# Adafruit_Circuit_Playground_Bluefruit.net
KiCad netlist of a schematic drawn in EAGLE
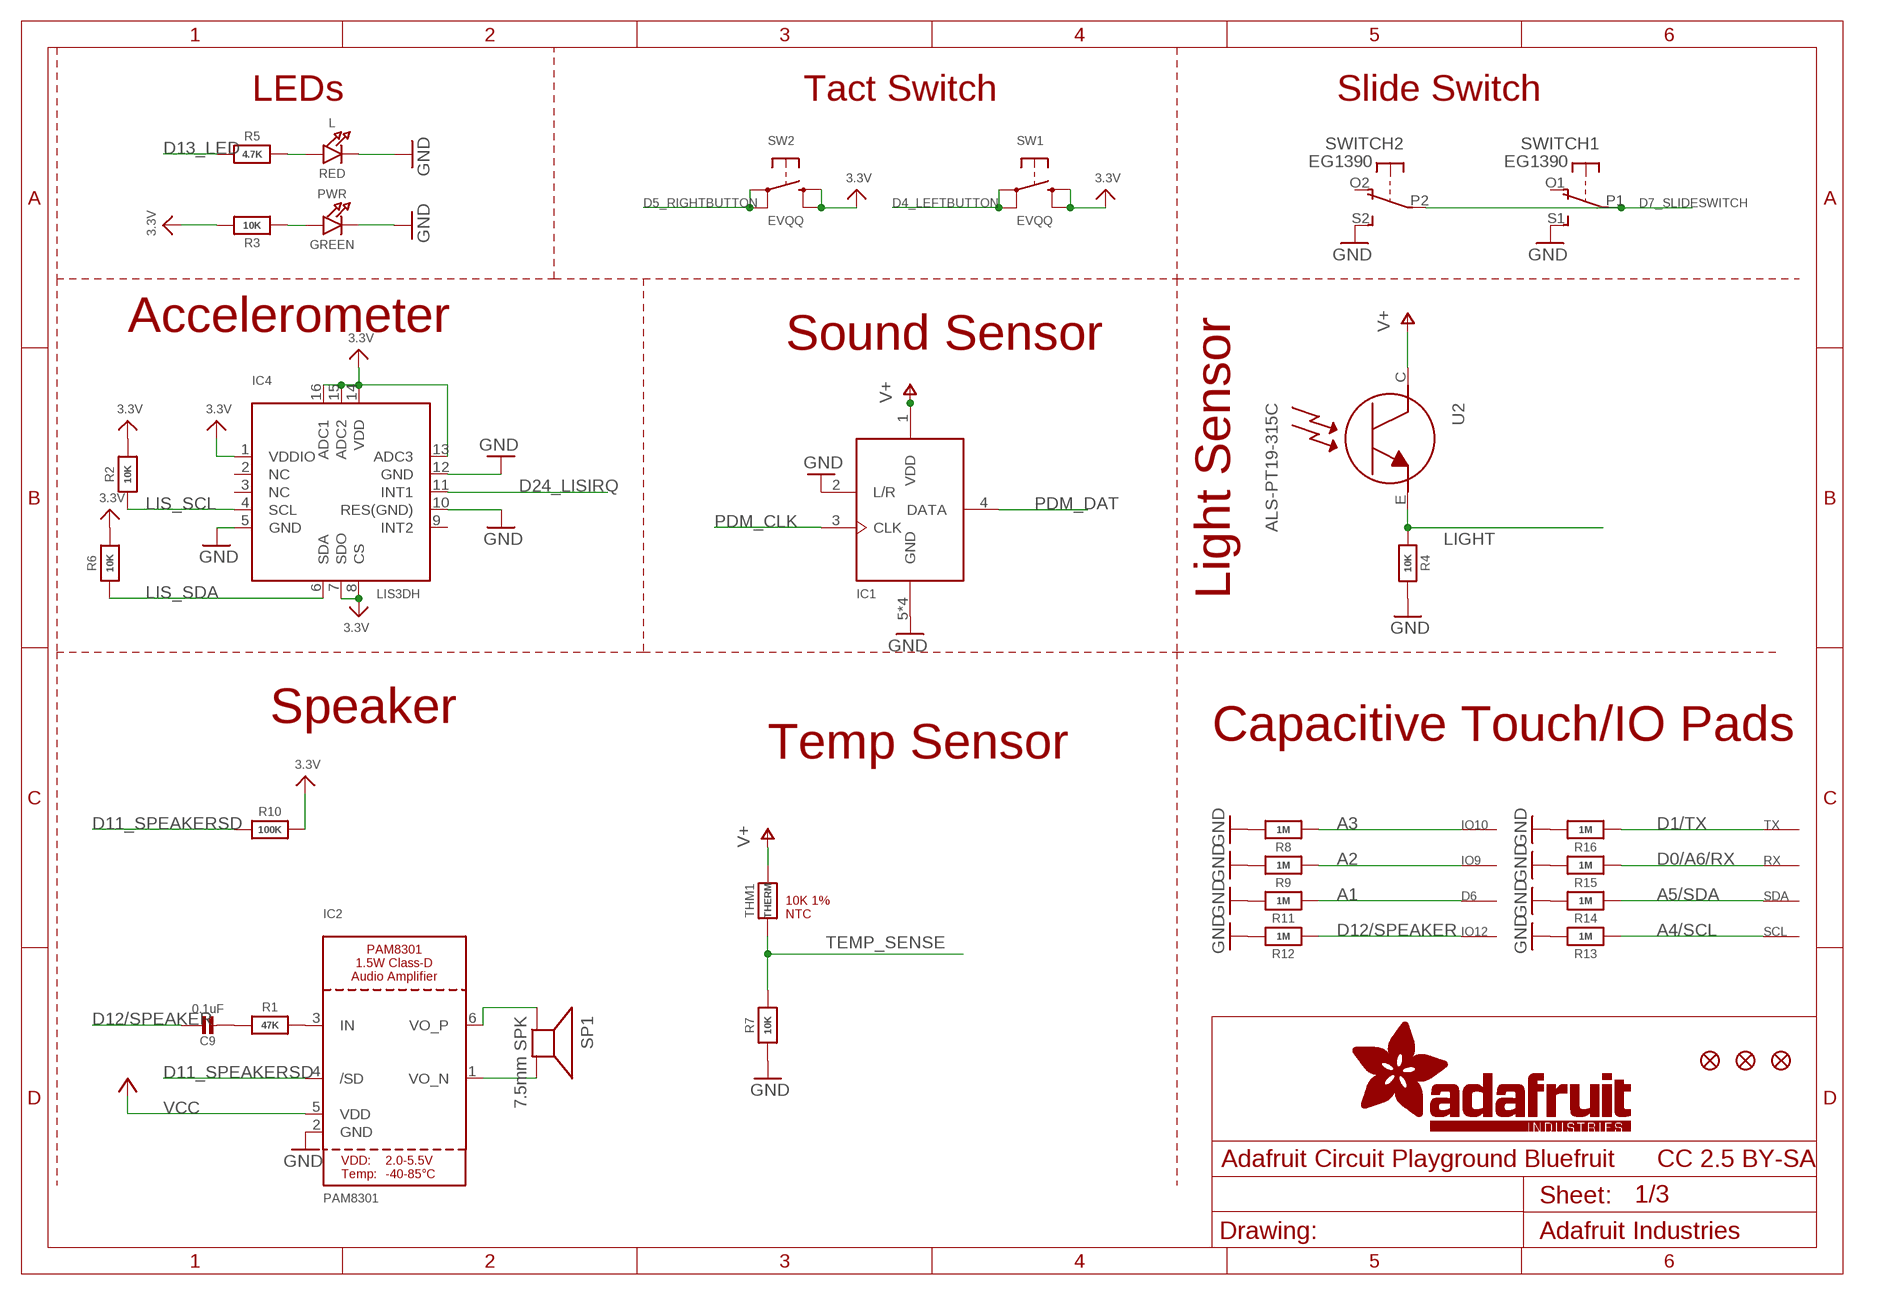
[diagram p0: schematic, sheet 1]
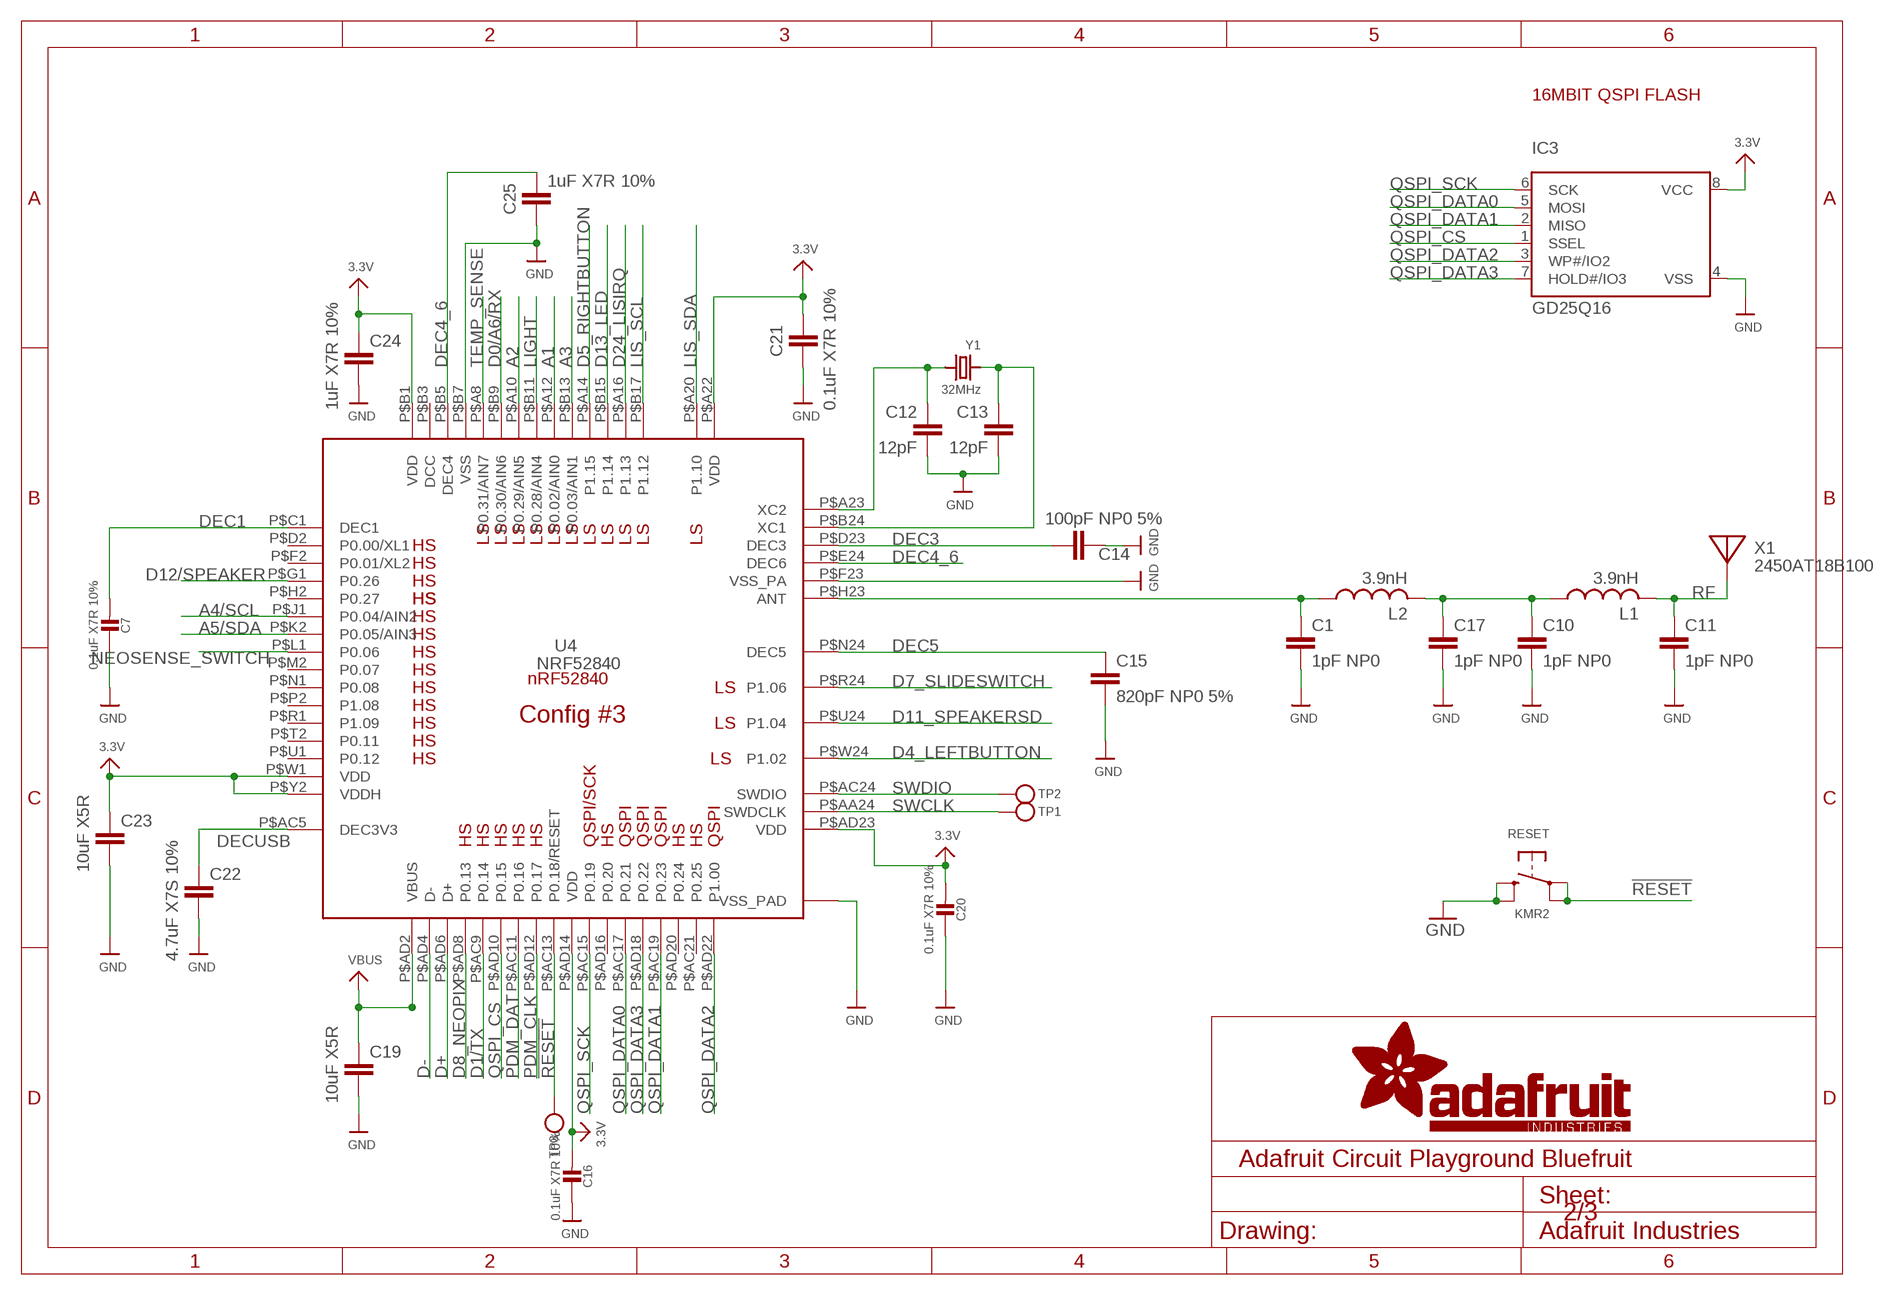
[diagram p1: schematic, sheet 2]
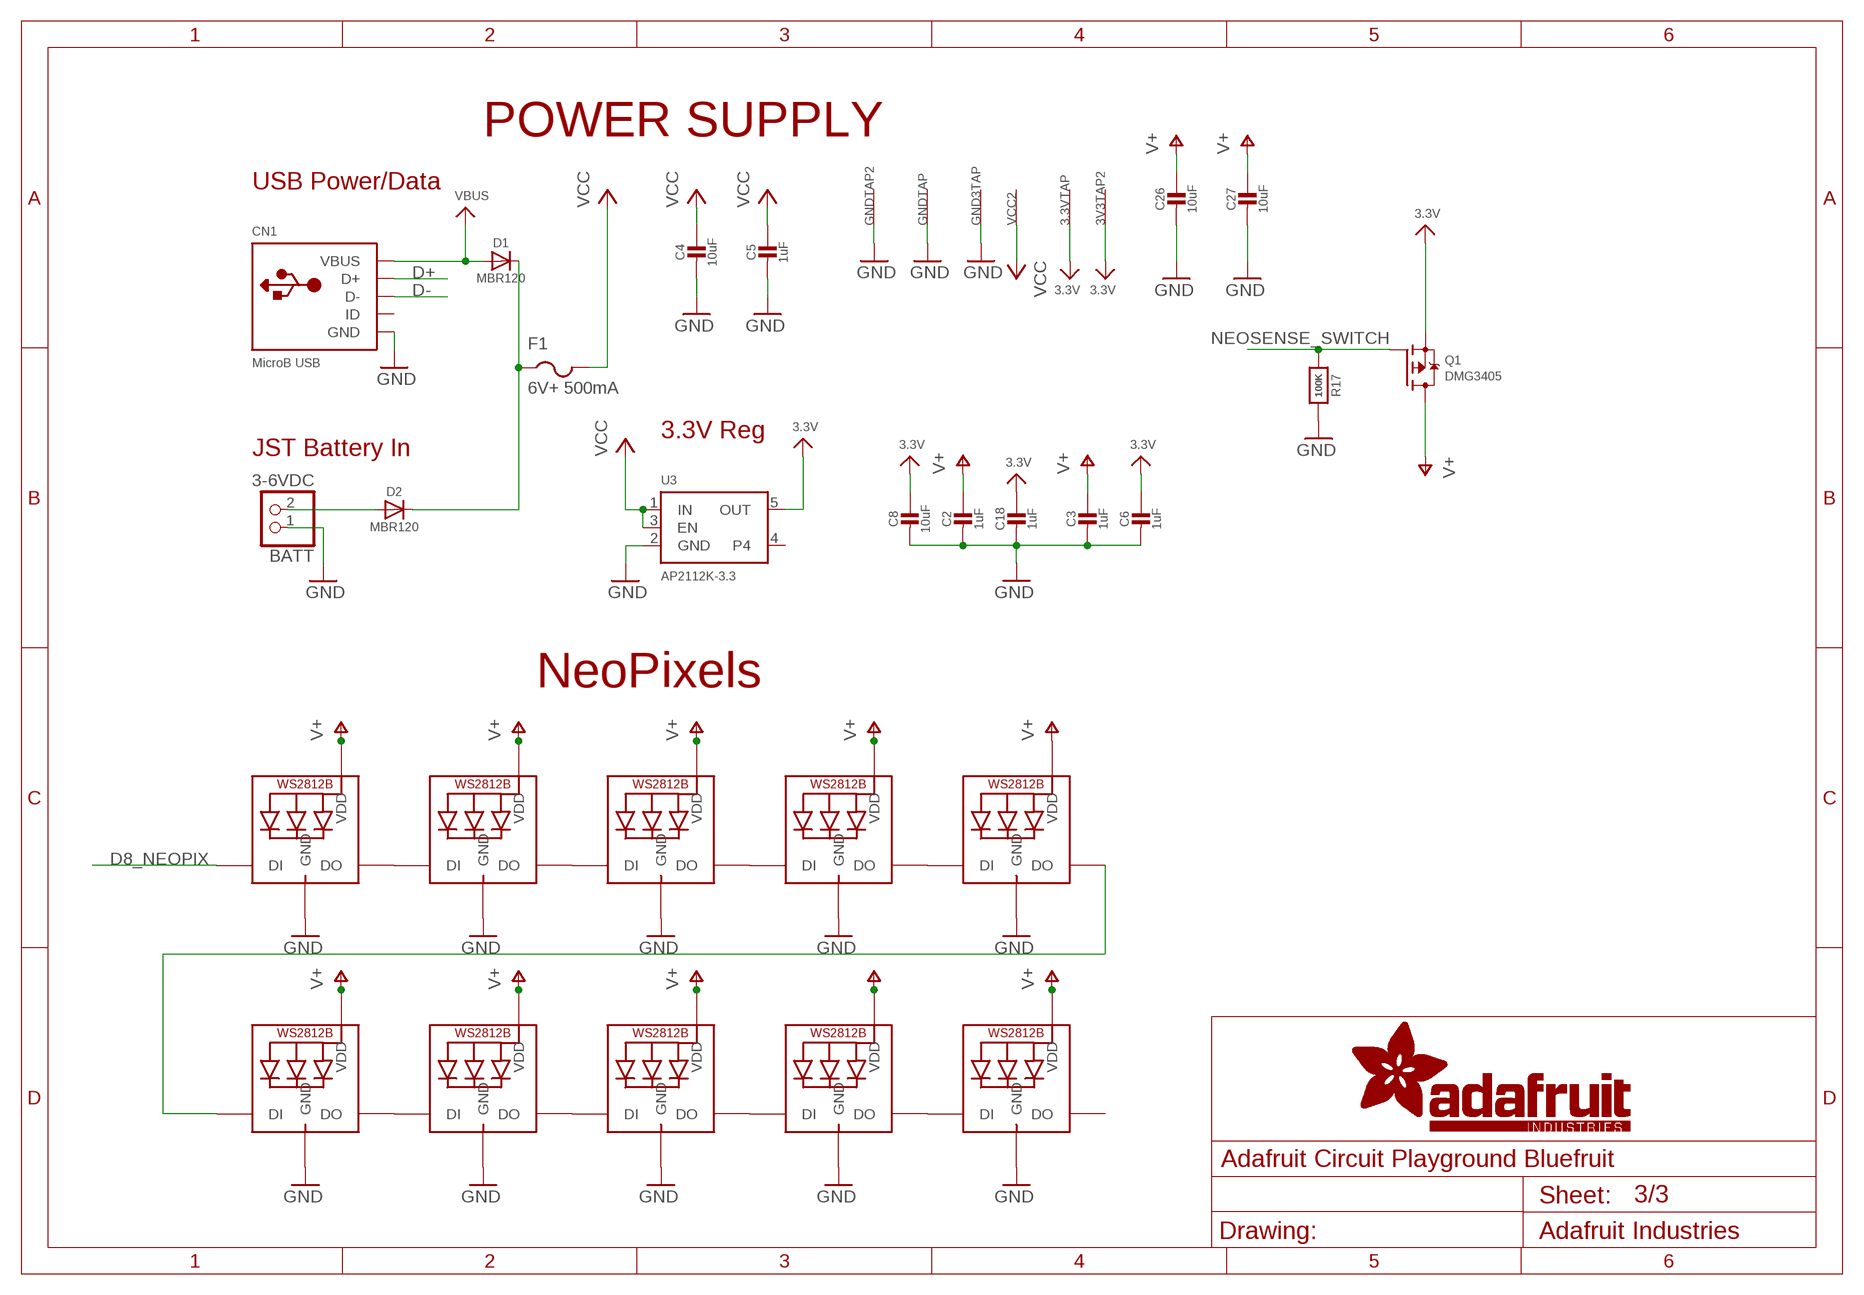
[diagram p2: schematic, sheet 3]

(export (version "E")
  (design (tool "Eeschema 10.0.6"))
  (components
    (comp (ref "C1")
      (value "1pF NP0")
      (footprint "eagle-import:RESC0402_N")
      (libsource (lib "eagle-import") (part "CAPACITOR_0402_N"))
    )
    (comp (ref "C7")
      (value "0.1uF X7R 10%")
      (footprint "eagle-import:0603-NO")
      (libsource (lib "eagle-import") (part "CAP_CERAMIC0603_NO"))
    )
    (comp (ref "C10")
      (value "1pF NP0")
      (footprint "eagle-import:RESC0402_N")
      (libsource (lib "eagle-import") (part "CAPACITOR_0402_N"))
    )
    (comp (ref "C11")
      (value "1pF NP0")
      (footprint "eagle-import:RESC0402_N")
      (libsource (lib "eagle-import") (part "CAPACITOR_0402_N"))
    )
    (comp (ref "C12")
      (value "12pF")
      (footprint "eagle-import:RESC0402_N")
      (libsource (lib "eagle-import") (part "CAPACITOR_0402_N"))
    )
    (comp (ref "C13")
      (value "12pF")
      (footprint "eagle-import:RESC0402_N")
      (libsource (lib "eagle-import") (part "CAPACITOR_0402_N"))
    )
    (comp (ref "C14")
      (value "100pF NP0 5%")
      (footprint "eagle-import:RESC0402_N")
      (libsource (lib "eagle-import") (part "CAPACITOR_0402_N"))
    )
    (comp (ref "C15")
      (value "820pF NP0 5%")
      (footprint "eagle-import:RESC0402_N")
      (libsource (lib "eagle-import") (part "CAPACITOR_0402_N"))
    )
    (comp (ref "C16")
      (value "0.1uF X7R 10%")
      (footprint "eagle-import:0603-NO")
      (libsource (lib "eagle-import") (part "CAP_CERAMIC0603_NO"))
    )
    (comp (ref "C17")
      (value "1pF NP0")
      (footprint "eagle-import:RESC0402_N")
      (libsource (lib "eagle-import") (part "CAPACITOR_0402_N"))
    )
    (comp (ref "C19")
      (value "10uF X5R")
      (footprint "eagle-import:RESC0805_N")
      (libsource (lib "eagle-import") (part "CAPACITOR_0805_N"))
    )
    (comp (ref "C20")
      (value "0.1uF X7R 10%")
      (footprint "eagle-import:0603-NO")
      (libsource (lib "eagle-import") (part "CAP_CERAMIC0603_NO"))
    )
    (comp (ref "C21")
      (value "0.1uF X7R 10%")
      (footprint "eagle-import:RESC0603_L")
      (libsource (lib "eagle-import") (part "CAPACITOR_0603_L"))
    )
    (comp (ref "C22")
      (value "4.7uF X7S 10%")
      (footprint "eagle-import:RESC0805_N")
      (libsource (lib "eagle-import") (part "CAPACITOR_0805_N"))
    )
    (comp (ref "C23")
      (value "10uF X5R")
      (footprint "eagle-import:RESC0805_N")
      (libsource (lib "eagle-import") (part "CAPACITOR_0805_N"))
    )
    (comp (ref "C24")
      (value "1uF X7R 10%")
      (footprint "eagle-import:RESC0603_N")
      (libsource (lib "eagle-import") (part "CAPACITOR_0603_N"))
    )
    (comp (ref "C25")
      (value "1uF X7R 10%")
      (footprint "eagle-import:RESC0603_N")
      (libsource (lib "eagle-import") (part "CAPACITOR_0603_N"))
    )
    (comp (ref "IC3")
      (value "GD25Q16")
      (footprint "eagle-import:USON8")
      (libsource (lib "eagle-import") (part "SPIFLASH_8PINUX"))
    )
    (comp (ref "L1")
      (value "3.9nH")
      (footprint "eagle-import:RESC0402_N")
      (libsource (lib "eagle-import") (part "INDUCTOR_0402_N"))
    )
    (comp (ref "L2")
      (value "3.9nH")
      (footprint "eagle-import:RESC0402_N")
      (libsource (lib "eagle-import") (part "INDUCTOR_0402_N"))
    )
    (comp (ref "RESET")
      (value "KMR2")
      (footprint "eagle-import:BTN_KMR2_4.6X2.8")
      (libsource (lib "eagle-import") (part "SWITCH_TACT_SMT4.6X2.8"))
    )
    (comp (ref "TP1")
      (value "TESTPOINTROUND1.5MMNO")
      (footprint "eagle-import:TESTPOINT_ROUND_1.5MM_NO")
      (libsource (lib "eagle-import") (part "TESTPOINTROUND1.5MMNO"))
    )
    (comp (ref "TP2")
      (value "TESTPOINTROUND1.5MMNO")
      (footprint "eagle-import:TESTPOINT_ROUND_1.5MM_NO")
      (libsource (lib "eagle-import") (part "TESTPOINTROUND1.5MMNO"))
    )
    (comp (ref "TP3")
      (value "TESTPOINTROUND1.5MMNO")
      (footprint "eagle-import:TESTPOINT_ROUND_1.5MM_NO")
      (libsource (lib "eagle-import") (part "TESTPOINTROUND1.5MMNO"))
    )
    (comp (ref "U4")
      (value "NRF52840")
      (footprint "eagle-import:AQFN50P700X800X85_HS-74N_SMALLCENTER")
      (libsource (lib "eagle-import") (part "NRF52840_CPB_SMALLCENTER"))
    )
    (comp (ref "X1")
      (value "2450AT18B100")
      (footprint "eagle-import:ANT_2450AT18B100")
      (libsource (lib "eagle-import") (part "ANTENNA_JOHANSON_2450AT18B100"))
    )
    (comp (ref "Y1")
      (value "32MHz")
      (footprint "eagle-import:CRYSTAL_2X1.6")
      (libsource (lib "eagle-import") (part "CRYSTAL_2X1.6MM"))
    )
    (comp (ref "C9")
      (value "0.1uF")
      (footprint "eagle-import:0603-NO")
      (libsource (lib "eagle-import") (part "CAP_CERAMIC0603_NO"))
    )
    (comp (ref "D6")
      (value "SEWTAP-ALLIGATOR")
      (footprint "eagle-import:SEWALLI")
      (libsource (lib "eagle-import") (part "SEWTAP-ALLIGATOR"))
    )
    (comp (ref "IC1")
      (value "MIC_PDM")
      (footprint "eagle-import:SPK0415HM4H")
      (libsource (lib "eagle-import") (part "MIC_PDM_SPK0415"))
    )
    (comp (ref "IC2")
      (value "PAM8301")
      (footprint "eagle-import:SOT23-6")
      (libsource (lib "eagle-import") (part "PAM8301"))
    )
    (comp (ref "IC4")
      (value "LIS3DH")
      (footprint "eagle-import:LGA16_3X3MM")
      (libsource (lib "eagle-import") (part "ACCEL_LIS3DHTR"))
    )
    (comp (ref "IO9")
      (value "SEWTAP-ALLIGATOR")
      (footprint "eagle-import:SEWALLI")
      (libsource (lib "eagle-import") (part "SEWTAP-ALLIGATOR"))
    )
    (comp (ref "IO10")
      (value "SEWTAP-ALLIGATOR")
      (footprint "eagle-import:SEWALLI")
      (libsource (lib "eagle-import") (part "SEWTAP-ALLIGATOR"))
    )
    (comp (ref "IO12")
      (value "SEWTAP-ALLIGATOR")
      (footprint "eagle-import:SEWALLI")
      (libsource (lib "eagle-import") (part "SEWTAP-ALLIGATOR"))
    )
    (comp (ref "L")
      (value "RED")
      (footprint "eagle-import:CHIPLED_0603_NOOUTLINE")
      (libsource (lib "eagle-import") (part "LED0603_NOOUTLINE"))
    )
    (comp (ref "PWR")
      (value "GREEN")
      (footprint "eagle-import:CHIPLED_0603_NOOUTLINE")
      (libsource (lib "eagle-import") (part "LED0603_NOOUTLINE"))
    )
    (comp (ref "R1")
      (value "47K")
      (footprint "eagle-import:0603-NO")
      (libsource (lib "eagle-import") (part "RESISTOR_0603_NOOUT"))
    )
    (comp (ref "R2")
      (value "10K")
      (footprint "eagle-import:0603-NO")
      (libsource (lib "eagle-import") (part "RESISTOR_0603_NOOUT"))
    )
    (comp (ref "R3")
      (value "10K")
      (footprint "eagle-import:0603-NO")
      (libsource (lib "eagle-import") (part "RESISTOR_0603_NOOUT"))
    )
    (comp (ref "R4")
      (value "10K")
      (footprint "eagle-import:0603-NO")
      (libsource (lib "eagle-import") (part "RESISTOR_0603_NOOUT"))
    )
    (comp (ref "R5")
      (value "4.7K")
      (footprint "eagle-import:0603-NO")
      (libsource (lib "eagle-import") (part "RESISTOR_0603_NOOUT"))
    )
    (comp (ref "R6")
      (value "10K")
      (footprint "eagle-import:0603-NO")
      (libsource (lib "eagle-import") (part "RESISTOR_0603_NOOUT"))
    )
    (comp (ref "R7")
      (value "10K")
      (footprint "eagle-import:0603-NO")
      (libsource (lib "eagle-import") (part "RESISTOR_0603_NOOUT"))
    )
    (comp (ref "R8")
      (value "1M")
      (footprint "eagle-import:0603-NO")
      (libsource (lib "eagle-import") (part "RESISTOR_0603_NOOUT"))
    )
    (comp (ref "R9")
      (value "1M")
      (footprint "eagle-import:0603-NO")
      (libsource (lib "eagle-import") (part "RESISTOR_0603_NOOUT"))
    )
    (comp (ref "R10")
      (value "100K")
      (footprint "eagle-import:0603-NO")
      (libsource (lib "eagle-import") (part "RESISTOR_0603_NOOUT"))
    )
    (comp (ref "R11")
      (value "1M")
      (footprint "eagle-import:0603-NO")
      (libsource (lib "eagle-import") (part "RESISTOR_0603_NOOUT"))
    )
    (comp (ref "R12")
      (value "1M")
      (footprint "eagle-import:0603-NO")
      (libsource (lib "eagle-import") (part "RESISTOR_0603_NOOUT"))
    )
    (comp (ref "R13")
      (value "1M")
      (footprint "eagle-import:0603-NO")
      (libsource (lib "eagle-import") (part "RESISTOR_0603_NOOUT"))
    )
    (comp (ref "R14")
      (value "1M")
      (footprint "eagle-import:0603-NO")
      (libsource (lib "eagle-import") (part "RESISTOR_0603_NOOUT"))
    )
    (comp (ref "R15")
      (value "1M")
      (footprint "eagle-import:0603-NO")
      (libsource (lib "eagle-import") (part "RESISTOR_0603_NOOUT"))
    )
    (comp (ref "R16")
      (value "1M")
      (footprint "eagle-import:0603-NO")
      (libsource (lib "eagle-import") (part "RESISTOR_0603_NOOUT"))
    )
    (comp (ref "RX")
      (value "SEWTAP-ALLIGATOR")
      (footprint "eagle-import:SEWALLI")
      (libsource (lib "eagle-import") (part "SEWTAP-ALLIGATOR"))
    )
    (comp (ref "SCL")
      (value "SEWTAP-ALLIGATOR")
      (footprint "eagle-import:SEWALLI")
      (libsource (lib "eagle-import") (part "SEWTAP-ALLIGATOR"))
    )
    (comp (ref "SDA")
      (value "SEWTAP-ALLIGATOR")
      (footprint "eagle-import:SEWALLI")
      (libsource (lib "eagle-import") (part "SEWTAP-ALLIGATOR"))
    )
    (comp (ref "SP1")
      (value "7.5mm SPK")
      (footprint "eagle-import:BUZZER_SMT_7.5MM")
      (libsource (lib "eagle-import") (part "SPEAKER_7.5MM"))
    )
    (comp (ref "SW1")
      (value "EVQQ")
      (footprint "eagle-import:EVQ-Q2_SMALLER")
      (libsource (lib "eagle-import") (part "SWITCH_TACT_SMT_EVQQ2_SMALL"))
    )
    (comp (ref "SW2")
      (value "EVQQ")
      (footprint "eagle-import:EVQ-Q2_SMALLER")
      (libsource (lib "eagle-import") (part "SWITCH_TACT_SMT_EVQQ2_SMALL"))
    )
    (comp (ref "SWITCH")
      (value "EG1390")
      (footprint "eagle-import:EG1390")
      (libsource (lib "eagle-import") (part "DPDT-EG1390"))
    )
    (comp (ref "THM1")
      (value "THERM")
      (footprint "eagle-import:_0402")
      (libsource (lib "eagle-import") (part "RESISTOR_0402"))
    )
    (comp (ref "TX")
      (value "SEWTAP-ALLIGATOR")
      (footprint "eagle-import:SEWALLI")
      (libsource (lib "eagle-import") (part "SEWTAP-ALLIGATOR"))
    )
    (comp (ref "U$2")
      (value "FIDUCIAL_1MM")
      (footprint "eagle-import:FIDUCIAL_1MM")
      (libsource (lib "eagle-import") (part "FIDUCIAL_1MM"))
    )
    (comp (ref "U$3")
      (value "FIDUCIAL_1MM")
      (footprint "eagle-import:FIDUCIAL_1MM")
      (fields (field (name "BOM") "EXCLUDE"))
      (libsource (lib "eagle-import") (part "FIDUCIAL_1MM"))
    )
    (comp (ref "U$6")
      (value "FIDUCIAL_1MM")
      (footprint "eagle-import:FIDUCIAL_1MM")
      (libsource (lib "eagle-import") (part "FIDUCIAL_1MM"))
    )
    (comp (ref "U2")
      (value "ALS-PT19-315C")
      (footprint "eagle-import:ALS-PT19-315C")
      (libsource (lib "eagle-import") (part "PHOTOTRANSISTOR_PT19-315C"))
    )
    (comp (ref "3.3VTAP")
      (value "SEWTAP-ALLIGATOR")
      (footprint "eagle-import:SEWALLI")
      (libsource (lib "eagle-import") (part "SEWTAP-ALLIGATOR"))
    )
    (comp (ref "3V3TAP2")
      (value "SEWTAP-ALLIGATOR")
      (footprint "eagle-import:SEWALLI")
      (libsource (lib "eagle-import") (part "SEWTAP-ALLIGATOR"))
    )
    (comp (ref "BATT")
      (value "3-6VDC")
      (footprint "eagle-import:JSTPH2")
      (libsource (lib "eagle-import") (part "CON_JST_PH_2PIN"))
    )
    (comp (ref "C2")
      (value "1uF")
      (footprint "eagle-import:0603-NO")
      (libsource (lib "eagle-import") (part "CAP_CERAMIC0603_NO"))
    )
    (comp (ref "C3")
      (value "1uF")
      (footprint "eagle-import:0603-NO")
      (libsource (lib "eagle-import") (part "CAP_CERAMIC0603_NO"))
    )
    (comp (ref "C4")
      (value "10uF")
      (footprint "eagle-import:0805-NO")
      (libsource (lib "eagle-import") (part "CAP_CERAMIC0805-NOOUTLINE"))
    )
    (comp (ref "C5")
      (value "1uF")
      (footprint "eagle-import:0603-NO")
      (libsource (lib "eagle-import") (part "CAP_CERAMIC0603_NO"))
    )
    (comp (ref "C6")
      (value "1uF")
      (footprint "eagle-import:0603-NO")
      (libsource (lib "eagle-import") (part "CAP_CERAMIC0603_NO"))
    )
    (comp (ref "C8")
      (value "10uF")
      (footprint "eagle-import:0805-NO")
      (libsource (lib "eagle-import") (part "CAP_CERAMIC0805-NOOUTLINE"))
    )
    (comp (ref "C18")
      (value "1uF")
      (footprint "eagle-import:0603-NO")
      (libsource (lib "eagle-import") (part "CAP_CERAMIC0603_NO"))
    )
    (comp (ref "C26")
      (value "10uF")
      (footprint "eagle-import:0805-NO")
      (libsource (lib "eagle-import") (part "CAP_CERAMIC0805-NOOUTLINE"))
    )
    (comp (ref "C27")
      (value "10uF")
      (footprint "eagle-import:0805-NO")
      (libsource (lib "eagle-import") (part "CAP_CERAMIC0805-NOOUTLINE"))
    )
    (comp (ref "CN1")
      (value "MicroB USB")
      (footprint "eagle-import:4UCONN_20329_V2")
      (libsource (lib "eagle-import") (part "USB_MICRO_20329_V2"))
    )
    (comp (ref "D1")
      (value "MBR120")
      (footprint "eagle-import:SOD-123")
      (libsource (lib "eagle-import") (part "DIODESOD-123"))
    )
    (comp (ref "D2")
      (value "MBR120")
      (footprint "eagle-import:SOD-123")
      (libsource (lib "eagle-import") (part "DIODESOD-123"))
    )
    (comp (ref "F1")
      (value "6V+ 500mA")
      (footprint "eagle-import:R1206")
      (libsource (lib "eagle-import") (part "PTCFUSE-1206"))
    )
    (comp (ref "GND3TAP")
      (value "SEWTAP-ALLIGATOR")
      (footprint "eagle-import:SEWALLI")
      (libsource (lib "eagle-import") (part "SEWTAP-ALLIGATOR"))
    )
    (comp (ref "GNDTAP")
      (value "SEWTAP-ALLIGATOR")
      (footprint "eagle-import:SEWALLI")
      (libsource (lib "eagle-import") (part "SEWTAP-ALLIGATOR"))
    )
    (comp (ref "GNDTAP2")
      (value "SEWTAP-ALLIGATOR")
      (footprint "eagle-import:SEWALLI")
      (libsource (lib "eagle-import") (part "SEWTAP-ALLIGATOR"))
    )
    (comp (ref "LED1")
      (value "WS2812B3535")
      (footprint "eagle-import:LED3535")
      (libsource (lib "eagle-import") (part "WS2812B3535"))
    )
    (comp (ref "LED2")
      (value "WS2812B3535")
      (footprint "eagle-import:LED3535")
      (libsource (lib "eagle-import") (part "WS2812B3535"))
    )
    (comp (ref "LED3")
      (value "WS2812B3535")
      (footprint "eagle-import:LED3535")
      (libsource (lib "eagle-import") (part "WS2812B3535"))
    )
    (comp (ref "LED4")
      (value "WS2812B3535")
      (footprint "eagle-import:LED3535")
      (libsource (lib "eagle-import") (part "WS2812B3535"))
    )
    (comp (ref "LED5")
      (value "WS2812B3535")
      (footprint "eagle-import:LED3535")
      (libsource (lib "eagle-import") (part "WS2812B3535"))
    )
    (comp (ref "LED6")
      (value "WS2812B3535")
      (footprint "eagle-import:LED3535")
      (libsource (lib "eagle-import") (part "WS2812B3535"))
    )
    (comp (ref "LED7")
      (value "WS2812B3535")
      (footprint "eagle-import:LED3535")
      (libsource (lib "eagle-import") (part "WS2812B3535"))
    )
    (comp (ref "LED8")
      (value "WS2812B3535")
      (footprint "eagle-import:LED3535")
      (libsource (lib "eagle-import") (part "WS2812B3535"))
    )
    (comp (ref "LED9")
      (value "WS2812B3535")
      (footprint "eagle-import:LED3535")
      (libsource (lib "eagle-import") (part "WS2812B3535"))
    )
    (comp (ref "LED10")
      (value "WS2812B3535")
      (footprint "eagle-import:LED3535")
      (libsource (lib "eagle-import") (part "WS2812B3535"))
    )
    (comp (ref "Q1")
      (value "DMG3405")
      (footprint "eagle-import:SOT23-R")
      (libsource (lib "eagle-import") (part "MOSFET-P"))
    )
    (comp (ref "R17")
      (value "100K")
      (footprint "eagle-import:0603-NO")
      (libsource (lib "eagle-import") (part "RESISTOR_0603_NOOUT"))
    )
    (comp (ref "U3")
      (value "AP2112K-3.3")
      (footprint "eagle-import:SOT23-5")
      (libsource (lib "eagle-import") (part "VREG_SOT23-5"))
    )
    (comp (ref "VCC2")
      (value "SEWTAP-ALLIGATOR")
      (footprint "eagle-import:SEWALLI")
      (libsource (lib "eagle-import") (part "SEWTAP-ALLIGATOR"))
    )
  )
  (nets
    (net (code "1") (name "3.3V") (class "Default")
      (node (ref "3.3VTAP") (pin "P$1") (pinfunction "SEW_P$1") (pintype "bidirectional"))
      (node (ref "3V3TAP2") (pin "P$1") (pinfunction "SEW_P$1") (pintype "bidirectional"))
      (node (ref "C16") (pin "2") (pinfunction "2_2") (pintype "passive"))
      (node (ref "C18") (pin "1") (pinfunction "1_1") (pintype "passive"))
      (node (ref "C20") (pin "2") (pinfunction "2_2") (pintype "passive"))
      (node (ref "C21") (pin "1") (pinfunction "1_1") (pintype "passive"))
      (node (ref "C23") (pin "1") (pinfunction "1_1") (pintype "passive"))
      (node (ref "C24") (pin "1") (pinfunction "1_1") (pintype "passive"))
      (node (ref "C6") (pin "1") (pinfunction "1_1") (pintype "passive"))
      (node (ref "C8") (pin "1") (pinfunction "1_1") (pintype "passive"))
      (node (ref "IC3") (pin "8") (pinfunction "VCC_8") (pintype "bidirectional"))
      (node (ref "IC4") (pin "1") (pinfunction "VDDIO_1") (pintype "power_in"))
      (node (ref "IC4") (pin "13") (pinfunction "ADC3_13") (pintype "input"))
      (node (ref "IC4") (pin "14") (pinfunction "VDD_14") (pintype "power_in"))
      (node (ref "IC4") (pin "15") (pinfunction "ADC2_15") (pintype "input"))
      (node (ref "IC4") (pin "16") (pinfunction "ADC1_16") (pintype "input"))
      (node (ref "IC4") (pin "7") (pinfunction "SDO_7") (pintype "bidirectional"))
      (node (ref "IC4") (pin "8") (pinfunction "CS_8") (pintype "input"))
      (node (ref "Q1") (pin "2") (pinfunction "S_2") (pintype "passive"))
      (node (ref "R10") (pin "2") (pinfunction "2_2") (pintype "passive"))
      (node (ref "R2") (pin "2") (pinfunction "2_2") (pintype "passive"))
      (node (ref "R3") (pin "2") (pinfunction "2_2") (pintype "passive"))
      (node (ref "R6") (pin "2") (pinfunction "2_2") (pintype "passive"))
      (node (ref "SW1") (pin "B") (pinfunction "S_B") (pintype "passive"))
      (node (ref "SW1") (pin "B'") (pinfunction "S1_B'") (pintype "passive"))
      (node (ref "SW2") (pin "B") (pinfunction "S_B") (pintype "passive"))
      (node (ref "SW2") (pin "B'") (pinfunction "S1_B'") (pintype "passive"))
      (node (ref "U3") (pin "5") (pinfunction "OUT_5") (pintype "power_in"))
      (node (ref "U4") (pin "P$A22") (pinfunction "VDD_P$A22") (pintype "power_in"))
      (node (ref "U4") (pin "P$AD14") (pinfunction "VDD_P$AD14") (pintype "power_in"))
      (node (ref "U4") (pin "P$AD23") (pinfunction "VDD_P$AD23") (pintype "power_in"))
      (node (ref "U4") (pin "P$B1") (pinfunction "VDD_P$B1") (pintype "power_in"))
      (node (ref "U4") (pin "P$W1") (pinfunction "VDD_P$W1") (pintype "power_in"))
      (node (ref "U4") (pin "P$Y2") (pinfunction "VDDH_P$Y2") (pintype "power_in"))
    )
    (net (code "2") (name "A1") (class "Default")
      (node (ref "D6") (pin "P$1") (pinfunction "SEW_P$1") (pintype "bidirectional"))
      (node (ref "R11") (pin "1") (pinfunction "1_1") (pintype "passive"))
      (node (ref "U4") (pin "P$A12") (pinfunction "P0.02/AIN0_P$A12") (pintype "bidirectional"))
    )
    (net (code "3") (name "A2") (class "Default")
      (node (ref "IO9") (pin "P$1") (pinfunction "SEW_P$1") (pintype "bidirectional"))
      (node (ref "R9") (pin "1") (pinfunction "1_1") (pintype "passive"))
      (node (ref "U4") (pin "P$A10") (pinfunction "P0.29/AIN5_P$A10") (pintype "bidirectional"))
    )
    (net (code "4") (name "A3") (class "Default")
      (node (ref "IO10") (pin "P$1") (pinfunction "SEW_P$1") (pintype "bidirectional"))
      (node (ref "R8") (pin "1") (pinfunction "1_1") (pintype "passive"))
      (node (ref "U4") (pin "P$B13") (pinfunction "P0.03/AIN1_P$B13") (pintype "bidirectional"))
    )
    (net (code "5") (name "A4{slash}SCL") (class "Default")
      (node (ref "R13") (pin "1") (pinfunction "1_1") (pintype "passive"))
      (node (ref "SCL") (pin "P$1") (pinfunction "SEW_P$1") (pintype "bidirectional"))
      (node (ref "U4") (pin "P$J1") (pinfunction "P0.04/AIN2_P$J1") (pintype "bidirectional"))
    )
    (net (code "6") (name "A5{slash}SDA") (class "Default")
      (node (ref "R14") (pin "1") (pinfunction "1_1") (pintype "passive"))
      (node (ref "SDA") (pin "P$1") (pinfunction "SEW_P$1") (pintype "bidirectional"))
      (node (ref "U4") (pin "P$K2") (pinfunction "P0.05/AIN3_P$K2") (pintype "bidirectional"))
    )
    (net (code "7") (name "D+") (class "Default")
      (node (ref "CN1") (pin "D+") (pinfunction "D+_D+") (pintype "bidirectional"))
      (node (ref "U4") (pin "P$AD6") (pinfunction "D+_P$AD6") (pintype "bidirectional"))
    )
    (net (code "8") (name "D-") (class "Default")
      (node (ref "CN1") (pin "D-") (pinfunction "D-_D-") (pintype "bidirectional"))
      (node (ref "U4") (pin "P$AD4") (pinfunction "D-_P$AD4") (pintype "bidirectional"))
    )
    (net (code "9") (name "D0{slash}A6{slash}RX") (class "Default")
      (node (ref "R15") (pin "1") (pinfunction "1_1") (pintype "passive"))
      (node (ref "RX") (pin "P$1") (pinfunction "SEW_P$1") (pintype "bidirectional"))
      (node (ref "U4") (pin "P$B9") (pinfunction "P0.30/AIN6_P$B9") (pintype "bidirectional"))
    )
    (net (code "10") (name "D1{slash}TX") (class "Default")
      (node (ref "R16") (pin "1") (pinfunction "1_1") (pintype "passive"))
      (node (ref "TX") (pin "P$1") (pinfunction "SEW_P$1") (pintype "bidirectional"))
      (node (ref "U4") (pin "P$AC9") (pinfunction "P0.14_P$AC9") (pintype "bidirectional"))
    )
    (net (code "11") (name "D4_LEFTBUTTON") (class "Default")
      (node (ref "SW1") (pin "A") (pinfunction "P_A") (pintype "passive"))
      (node (ref "SW1") (pin "A'") (pinfunction "P1_A'") (pintype "passive"))
      (node (ref "U4") (pin "P$W24") (pinfunction "P1.02_P$W24") (pintype "bidirectional"))
    )
    (net (code "12") (name "D5_RIGHTBUTTON") (class "Default")
      (node (ref "SW2") (pin "A") (pinfunction "P_A") (pintype "passive"))
      (node (ref "SW2") (pin "A'") (pinfunction "P1_A'") (pintype "passive"))
      (node (ref "U4") (pin "P$A14") (pinfunction "P1.15_P$A14") (pintype "bidirectional"))
    )
    (net (code "13") (name "D7_SLIDESWITCH") (class "Default")
      (node (ref "SWITCH") (pin "P1") (pinfunction "P_P1") (pintype "passive"))
      (node (ref "SWITCH") (pin "P2") (pinfunction "P_P2") (pintype "passive"))
      (node (ref "U4") (pin "P$R24") (pinfunction "P1.06_P$R24") (pintype "bidirectional"))
    )
    (net (code "14") (name "D8_NEOPIX") (class "Default")
      (node (ref "LED6") (pin "1") (pinfunction "DI_1") (pintype "input"))
      (node (ref "U4") (pin "P$AD8") (pinfunction "P0.13_P$AD8") (pintype "bidirectional"))
    )
    (net (code "15") (name "D11_SPEAKERSD") (class "Default")
      (node (ref "IC2") (pin "4") (pinfunction "/SD_4") (pintype "input"))
      (node (ref "R10") (pin "1") (pinfunction "1_1") (pintype "passive"))
      (node (ref "U4") (pin "P$U24") (pinfunction "P1.04_P$U24") (pintype "bidirectional"))
    )
    (net (code "16") (name "D12{slash}SPEAKER") (class "Default")
      (node (ref "C9") (pin "1") (pinfunction "1_1") (pintype "passive"))
      (node (ref "IO12") (pin "P$1") (pinfunction "SEW_P$1") (pintype "bidirectional"))
      (node (ref "R12") (pin "1") (pinfunction "1_1") (pintype "passive"))
      (node (ref "U4") (pin "P$G1") (pinfunction "P0.26_P$G1") (pintype "bidirectional"))
    )
    (net (code "17") (name "D13_LED") (class "Default")
      (node (ref "R5") (pin "1") (pinfunction "1_1") (pintype "passive"))
      (node (ref "U4") (pin "P$B15") (pinfunction "P1.14_P$B15") (pintype "bidirectional"))
    )
    (net (code "18") (name "D24_LISIRQ") (class "Default")
      (node (ref "IC4") (pin "11") (pinfunction "INT1_11") (pintype "output"))
      (node (ref "U4") (pin "P$A16") (pinfunction "P1.13_P$A16") (pintype "bidirectional"))
    )
    (net (code "19") (name "DEC1") (class "Default")
      (node (ref "C7") (pin "2") (pinfunction "2_2") (pintype "passive"))
      (node (ref "U4") (pin "P$C1") (pinfunction "DEC1_P$C1") (pintype "power_in"))
    )
    (net (code "20") (name "DEC3") (class "Default")
      (node (ref "C14") (pin "1") (pinfunction "1_1") (pintype "passive"))
      (node (ref "U4") (pin "P$D23") (pinfunction "DEC3_P$D23") (pintype "bidirectional"))
    )
    (net (code "21") (name "DEC4_6") (class "Default")
      (node (ref "C25") (pin "1") (pinfunction "1_1") (pintype "passive"))
      (node (ref "U4") (pin "P$B5") (pinfunction "DEC4_P$B5") (pintype "power_in"))
      (node (ref "U4") (pin "P$E24") (pinfunction "DEC6_P$E24") (pintype "bidirectional"))
    )
    (net (code "22") (name "DEC5") (class "Default")
      (node (ref "C15") (pin "1") (pinfunction "1_1") (pintype "passive"))
      (node (ref "U4") (pin "P$N24") (pinfunction "DEC5_P$N24") (pintype "bidirectional"))
    )
    (net (code "23") (name "DECUSB") (class "Default")
      (node (ref "C22") (pin "1") (pinfunction "1_1") (pintype "passive"))
      (node (ref "U4") (pin "P$AC5") (pinfunction "DEC3V3_P$AC5") (pintype "bidirectional"))
    )
    (net (code "24") (name "GND") (class "Default")
      (node (ref "BATT") (pin "1") (pinfunction "1_1") (pintype "passive"))
      (node (ref "C1") (pin "2") (pinfunction "2_2") (pintype "passive"))
      (node (ref "C10") (pin "2") (pinfunction "2_2") (pintype "passive"))
      (node (ref "C11") (pin "2") (pinfunction "2_2") (pintype "passive"))
      (node (ref "C12") (pin "2") (pinfunction "2_2") (pintype "passive"))
      (node (ref "C13") (pin "2") (pinfunction "2_2") (pintype "passive"))
      (node (ref "C14") (pin "2") (pinfunction "2_2") (pintype "passive"))
      (node (ref "C15") (pin "2") (pinfunction "2_2") (pintype "passive"))
      (node (ref "C16") (pin "1") (pinfunction "1_1") (pintype "passive"))
      (node (ref "C17") (pin "2") (pinfunction "2_2") (pintype "passive"))
      (node (ref "C18") (pin "2") (pinfunction "2_2") (pintype "passive"))
      (node (ref "C19") (pin "2") (pinfunction "2_2") (pintype "passive"))
      (node (ref "C2") (pin "2") (pinfunction "2_2") (pintype "passive"))
      (node (ref "C20") (pin "1") (pinfunction "1_1") (pintype "passive"))
      (node (ref "C21") (pin "2") (pinfunction "2_2") (pintype "passive"))
      (node (ref "C22") (pin "2") (pinfunction "2_2") (pintype "passive"))
      (node (ref "C23") (pin "2") (pinfunction "2_2") (pintype "passive"))
      (node (ref "C24") (pin "2") (pinfunction "2_2") (pintype "passive"))
      (node (ref "C25") (pin "2") (pinfunction "2_2") (pintype "passive"))
      (node (ref "C26") (pin "2") (pinfunction "2_2") (pintype "passive"))
      (node (ref "C27") (pin "2") (pinfunction "2_2") (pintype "passive"))
      (node (ref "C3") (pin "2") (pinfunction "2_2") (pintype "passive"))
      (node (ref "C4") (pin "2") (pinfunction "2_2") (pintype "passive"))
      (node (ref "C5") (pin "2") (pinfunction "2_2") (pintype "passive"))
      (node (ref "C6") (pin "2") (pinfunction "2_2") (pintype "passive"))
      (node (ref "C7") (pin "1") (pinfunction "1_1") (pintype "passive"))
      (node (ref "C8") (pin "2") (pinfunction "2_2") (pintype "passive"))
      (node (ref "CN1") (pin "BASE@1") (pinfunction "GND_BASE@1") (pintype "power_in"))
      (node (ref "CN1") (pin "BASE@2") (pinfunction "GND_BASE@2") (pintype "power_in"))
      (node (ref "CN1") (pin "GND") (pinfunction "GND_GND") (pintype "power_in"))
      (node (ref "CN1") (pin "SPRT@1") (pinfunction "GND_SPRT@1") (pintype "power_in"))
      (node (ref "CN1") (pin "SPRT@2") (pinfunction "GND_SPRT@2") (pintype "power_in"))
      (node (ref "CN1") (pin "SPRT@3") (pinfunction "GND_SPRT@3") (pintype "power_in"))
      (node (ref "CN1") (pin "SPRT@4") (pinfunction "GND_SPRT@4") (pintype "power_in"))
      (node (ref "GND3TAP") (pin "P$1") (pinfunction "SEW_P$1") (pintype "bidirectional"))
      (node (ref "GNDTAP") (pin "P$1") (pinfunction "SEW_P$1") (pintype "bidirectional"))
      (node (ref "GNDTAP2") (pin "P$1") (pinfunction "SEW_P$1") (pintype "bidirectional"))
      (node (ref "IC1") (pin "2") (pinfunction "L/R_2") (pintype "input"))
      (node (ref "IC1") (pin "5") (pinfunction "GND_5") (pintype "power_in"))
      (node (ref "IC1") (pin "6") (pinfunction "GND_6") (pintype "power_in"))
      (node (ref "IC1") (pin "7") (pinfunction "GND_7") (pintype "power_in"))
      (node (ref "IC1") (pin "8") (pinfunction "GND_8") (pintype "power_in"))
      (node (ref "IC2") (pin "2") (pinfunction "GND_2") (pintype "power_in"))
      (node (ref "IC3") (pin "4") (pinfunction "VSS_4") (pintype "bidirectional"))
      (node (ref "IC4") (pin "10") (pinfunction "RES(GND)_10") (pintype "bidirectional"))
      (node (ref "IC4") (pin "12") (pinfunction "GND_12") (pintype "power_in"))
      (node (ref "IC4") (pin "5") (pinfunction "GND_5") (pintype "power_in"))
      (node (ref "L") (pin "C") (pinfunction "C_C") (pintype "passive"))
      (node (ref "LED1") (pin "4") (pinfunction "GND_4") (pintype "power_in"))
      (node (ref "LED10") (pin "4") (pinfunction "GND_4") (pintype "power_in"))
      (node (ref "LED2") (pin "4") (pinfunction "GND_4") (pintype "power_in"))
      (node (ref "LED3") (pin "4") (pinfunction "GND_4") (pintype "power_in"))
      (node (ref "LED4") (pin "4") (pinfunction "GND_4") (pintype "power_in"))
      (node (ref "LED5") (pin "4") (pinfunction "GND_4") (pintype "power_in"))
      (node (ref "LED6") (pin "4") (pinfunction "GND_4") (pintype "power_in"))
      (node (ref "LED7") (pin "4") (pinfunction "GND_4") (pintype "power_in"))
      (node (ref "LED8") (pin "4") (pinfunction "GND_4") (pintype "power_in"))
      (node (ref "LED9") (pin "4") (pinfunction "GND_4") (pintype "power_in"))
      (node (ref "PWR") (pin "C") (pinfunction "C_C") (pintype "passive"))
      (node (ref "R11") (pin "2") (pinfunction "2_2") (pintype "passive"))
      (node (ref "R12") (pin "2") (pinfunction "2_2") (pintype "passive"))
      (node (ref "R13") (pin "2") (pinfunction "2_2") (pintype "passive"))
      (node (ref "R14") (pin "2") (pinfunction "2_2") (pintype "passive"))
      (node (ref "R15") (pin "2") (pinfunction "2_2") (pintype "passive"))
      (node (ref "R16") (pin "2") (pinfunction "2_2") (pintype "passive"))
      (node (ref "R17") (pin "2") (pinfunction "2_2") (pintype "passive"))
      (node (ref "R4") (pin "1") (pinfunction "1_1") (pintype "passive"))
      (node (ref "R7") (pin "1") (pinfunction "1_1") (pintype "passive"))
      (node (ref "R8") (pin "2") (pinfunction "2_2") (pintype "passive"))
      (node (ref "R9") (pin "2") (pinfunction "2_2") (pintype "passive"))
      (node (ref "RESET") (pin "B") (pinfunction "S_B") (pintype "passive"))
      (node (ref "RESET") (pin "B'") (pinfunction "S1_B'") (pintype "passive"))
      (node (ref "SWITCH") (pin "S1") (pinfunction "S_S1") (pintype "passive"))
      (node (ref "SWITCH") (pin "S2") (pinfunction "S_S2") (pintype "passive"))
      (node (ref "U3") (pin "2") (pinfunction "GND_2") (pintype "power_in"))
      (node (ref "U4") (pin "P$B7") (pinfunction "VSS_P$B7") (pintype "power_in"))
      (node (ref "U4") (pin "P$F23") (pinfunction "VSS_PA_P$F23") (pintype "bidirectional"))
      (node (ref "U4") (pin "THERMPAD") (pinfunction "VSS_PAD_THERMPAD") (pintype "bidirectional"))
    )
    (net (code "25") (name "LIGHT") (class "Default")
      (node (ref "R4") (pin "2") (pinfunction "2_2") (pintype "passive"))
      (node (ref "U2") (pin "E") (pinfunction "E_E") (pintype "bidirectional"))
      (node (ref "U4") (pin "P$B11") (pinfunction "P0.28/AIN4_P$B11") (pintype "bidirectional"))
    )
    (net (code "26") (name "LIS_SCL") (class "Default")
      (node (ref "IC4") (pin "4") (pinfunction "SCL_4") (pintype "bidirectional"))
      (node (ref "R2") (pin "1") (pinfunction "1_1") (pintype "passive"))
      (node (ref "U4") (pin "P$B17") (pinfunction "P1.12_P$B17") (pintype "bidirectional"))
    )
    (net (code "27") (name "LIS_SDA") (class "Default")
      (node (ref "IC4") (pin "6") (pinfunction "SDA_6") (pintype "bidirectional"))
      (node (ref "R6") (pin "1") (pinfunction "1_1") (pintype "passive"))
      (node (ref "U4") (pin "P$A20") (pinfunction "P1.10_P$A20") (pintype "bidirectional"))
    )
    (net (code "28") (name "NEOSENSE_SWITCH") (class "Default")
      (node (ref "Q1") (pin "1") (pinfunction "G_1") (pintype "passive"))
      (node (ref "R17") (pin "1") (pinfunction "1_1") (pintype "passive"))
      (node (ref "U4") (pin "P$L1") (pinfunction "P0.06_P$L1") (pintype "bidirectional"))
    )
    (net (code "29") (name "Net-(BATT-Pad2)") (class "Default")
      (node (ref "BATT") (pin "2") (pinfunction "2_2") (pintype "passive"))
      (node (ref "D2") (pin "A") (pinfunction "A_A") (pintype "passive"))
    )
    (net (code "30") (name "Net-(C9-Pad2)") (class "Default")
      (node (ref "C9") (pin "2") (pinfunction "2_2") (pintype "passive"))
      (node (ref "R1") (pin "1") (pinfunction "1_1") (pintype "passive"))
    )
    (net (code "31") (name "Net-(C10-Pad1)") (class "Default")
      (node (ref "C10") (pin "1") (pinfunction "1_1") (pintype "passive"))
      (node (ref "C17") (pin "1") (pinfunction "1_1") (pintype "passive"))
      (node (ref "L1") (pin "1") (pinfunction "1_1") (pintype "passive"))
      (node (ref "L2") (pin "2") (pinfunction "2_2") (pintype "passive"))
    )
    (net (code "32") (name "Net-(D1-PadC)") (class "Default")
      (node (ref "D1") (pin "C") (pinfunction "C_C") (pintype "passive"))
      (node (ref "D2") (pin "C") (pinfunction "C_C") (pintype "passive"))
      (node (ref "F1") (pin "1") (pinfunction "1_1") (pintype "passive"))
    )
    (net (code "33") (name "Net-(IC2-IN)") (class "Default")
      (node (ref "IC2") (pin "3") (pinfunction "IN_3") (pintype "input"))
      (node (ref "R1") (pin "2") (pinfunction "2_2") (pintype "passive"))
    )
    (net (code "34") (name "Net-(IC2-VO_N)") (class "Default")
      (node (ref "IC2") (pin "1") (pinfunction "VO_N_1") (pintype "output"))
      (node (ref "SP1") (pin "-") (pinfunction "-_-") (pintype "passive"))
    )
    (net (code "35") (name "Net-(IC2-VO_P)") (class "Default")
      (node (ref "IC2") (pin "6") (pinfunction "VO_P_6") (pintype "output"))
      (node (ref "SP1") (pin "+") (pinfunction "+_+") (pintype "passive"))
    )
    (net (code "36") (name "Net-(L-PadA)") (class "Default")
      (node (ref "L") (pin "A") (pinfunction "A_A") (pintype "passive"))
      (node (ref "R5") (pin "2") (pinfunction "2_2") (pintype "passive"))
    )
    (net (code "37") (name "Net-(LED1-DI)") (class "Default")
      (node (ref "LED1") (pin "1") (pinfunction "DI_1") (pintype "input"))
      (node (ref "LED2") (pin "3") (pinfunction "DO_3") (pintype "output"))
    )
    (net (code "38") (name "Net-(LED1-DO)") (class "Default")
      (node (ref "LED1") (pin "3") (pinfunction "DO_3") (pintype "output"))
      (node (ref "LED3") (pin "1") (pinfunction "DI_1") (pintype "input"))
    )
    (net (code "39") (name "Net-(LED3-DO)") (class "Default")
      (node (ref "LED3") (pin "3") (pinfunction "DO_3") (pintype "output"))
      (node (ref "LED4") (pin "1") (pinfunction "DI_1") (pintype "input"))
    )
    (net (code "40") (name "Net-(LED4-DO)") (class "Default")
      (node (ref "LED4") (pin "3") (pinfunction "DO_3") (pintype "output"))
      (node (ref "LED5") (pin "1") (pinfunction "DI_1") (pintype "input"))
    )
    (net (code "41") (name "Net-(LED6-DO)") (class "Default")
      (node (ref "LED6") (pin "3") (pinfunction "DO_3") (pintype "output"))
      (node (ref "LED7") (pin "1") (pinfunction "DI_1") (pintype "input"))
    )
    (net (code "42") (name "Net-(LED7-DO)") (class "Default")
      (node (ref "LED7") (pin "3") (pinfunction "DO_3") (pintype "output"))
      (node (ref "LED8") (pin "1") (pinfunction "DI_1") (pintype "input"))
    )
    (net (code "43") (name "Net-(LED8-DO)") (class "Default")
      (node (ref "LED8") (pin "3") (pinfunction "DO_3") (pintype "output"))
      (node (ref "LED9") (pin "1") (pinfunction "DI_1") (pintype "input"))
    )
    (net (code "44") (name "Net-(LED10-DI)") (class "Default")
      (node (ref "LED10") (pin "1") (pinfunction "DI_1") (pintype "input"))
      (node (ref "LED9") (pin "3") (pinfunction "DO_3") (pintype "output"))
    )
    (net (code "45") (name "Net-(LED10-DO)") (class "Default")
      (node (ref "LED10") (pin "3") (pinfunction "DO_3") (pintype "output"))
      (node (ref "LED2") (pin "1") (pinfunction "DI_1") (pintype "input"))
    )
    (net (code "46") (name "Net-(PWR-PadA)") (class "Default")
      (node (ref "PWR") (pin "A") (pinfunction "A_A") (pintype "passive"))
      (node (ref "R3") (pin "1") (pinfunction "1_1") (pintype "passive"))
    )
    (net (code "47") (name "Net-(U4-ANT)") (class "Default")
      (node (ref "C1") (pin "1") (pinfunction "1_1") (pintype "passive"))
      (node (ref "L2") (pin "1") (pinfunction "1_1") (pintype "passive"))
      (node (ref "U4") (pin "P$H23") (pinfunction "ANT_P$H23") (pintype "bidirectional"))
    )
    (net (code "48") (name "Net-(U4-XC1)") (class "Default")
      (node (ref "C13") (pin "1") (pinfunction "1_1") (pintype "passive"))
      (node (ref "U4") (pin "P$B24") (pinfunction "XC1_P$B24") (pintype "input"))
      (node (ref "Y1") (pin "1") (pinfunction "1_1") (pintype "passive"))
    )
    (net (code "49") (name "Net-(U4-XC2)") (class "Default")
      (node (ref "C12") (pin "1") (pinfunction "1_1") (pintype "passive"))
      (node (ref "U4") (pin "P$A23") (pinfunction "XC2_P$A23") (pintype "output"))
      (node (ref "Y1") (pin "3") (pinfunction "2_3") (pintype "passive"))
    )
    (net (code "50") (name "PDM_CLK") (class "Default")
      (node (ref "IC1") (pin "3") (pinfunction "CLK_3") (pintype "input"))
      (node (ref "U4") (pin "P$AD12") (pinfunction "P0.17_P$AD12") (pintype "bidirectional"))
    )
    (net (code "51") (name "PDM_DAT") (class "Default")
      (node (ref "IC1") (pin "4") (pinfunction "DATA_4") (pintype "bidirectional"))
      (node (ref "U4") (pin "P$AC11") (pinfunction "P0.16_P$AC11") (pintype "bidirectional"))
    )
    (net (code "52") (name "QSPI_CS") (class "Default")
      (node (ref "IC3") (pin "1") (pinfunction "SSEL_1") (pintype "bidirectional"))
      (node (ref "U4") (pin "P$AD10") (pinfunction "P0.15_P$AD10") (pintype "bidirectional"))
    )
    (net (code "53") (name "QSPI_DATA0") (class "Default")
      (node (ref "IC3") (pin "5") (pinfunction "MOSI_5") (pintype "bidirectional"))
      (node (ref "U4") (pin "P$AC17") (pinfunction "P0.21_P$AC17") (pintype "bidirectional"))
    )
    (net (code "54") (name "QSPI_DATA1") (class "Default")
      (node (ref "IC3") (pin "2") (pinfunction "MISO_2") (pintype "bidirectional"))
      (node (ref "U4") (pin "P$AC19") (pinfunction "P0.23_P$AC19") (pintype "bidirectional"))
    )
    (net (code "55") (name "QSPI_DATA2") (class "Default")
      (node (ref "IC3") (pin "3") (pinfunction "WP#/IO2_3") (pintype "bidirectional"))
      (node (ref "U4") (pin "P$AD22") (pinfunction "P1.00_P$AD22") (pintype "bidirectional"))
    )
    (net (code "56") (name "QSPI_DATA3") (class "Default")
      (node (ref "IC3") (pin "7") (pinfunction "HOLD#/IO3_7") (pintype "bidirectional"))
      (node (ref "U4") (pin "P$AD18") (pinfunction "P0.22_P$AD18") (pintype "bidirectional"))
    )
    (net (code "57") (name "QSPI_SCK") (class "Default")
      (node (ref "IC3") (pin "6") (pinfunction "SCK_6") (pintype "bidirectional"))
      (node (ref "U4") (pin "P$AC15") (pinfunction "P0.19_P$AC15") (pintype "bidirectional"))
    )
    (net (code "58") (name "RF") (class "Default")
      (node (ref "C11") (pin "1") (pinfunction "1_1") (pintype "passive"))
      (node (ref "L1") (pin "2") (pinfunction "2_2") (pintype "passive"))
      (node (ref "X1") (pin "FP") (pinfunction "P$1_FP") (pintype "passive"))
    )
    (net (code "59") (name "SWCLK") (class "Default")
      (node (ref "TP1") (pin "P$1") (pinfunction "P$1_P$1") (pintype "bidirectional"))
      (node (ref "U4") (pin "P$AA24") (pinfunction "SWDCLK_P$AA24") (pintype "input"))
    )
    (net (code "60") (name "SWDIO") (class "Default")
      (node (ref "TP2") (pin "P$1") (pinfunction "P$1_P$1") (pintype "bidirectional"))
      (node (ref "U4") (pin "P$AC24") (pinfunction "SWDIO_P$AC24") (pintype "bidirectional"))
    )
    (net (code "61") (name "TEMP_SENSE") (class "Default")
      (node (ref "R7") (pin "2") (pinfunction "2_2") (pintype "passive"))
      (node (ref "THM1") (pin "1") (pinfunction "1_1") (pintype "passive"))
      (node (ref "U4") (pin "P$A8") (pinfunction "P0.31/AIN7_P$A8") (pintype "bidirectional"))
    )
    (net (code "62") (name "V+") (class "Default")
      (node (ref "C2") (pin "1") (pinfunction "1_1") (pintype "passive"))
      (node (ref "C26") (pin "1") (pinfunction "1_1") (pintype "passive"))
      (node (ref "C27") (pin "1") (pinfunction "1_1") (pintype "passive"))
      (node (ref "C3") (pin "1") (pinfunction "1_1") (pintype "passive"))
      (node (ref "IC1") (pin "1") (pinfunction "VDD_1") (pintype "power_in"))
      (node (ref "LED1") (pin "2") (pinfunction "VDD_2") (pintype "power_in"))
      (node (ref "LED10") (pin "2") (pinfunction "VDD_2") (pintype "power_in"))
      (node (ref "LED2") (pin "2") (pinfunction "VDD_2") (pintype "power_in"))
      (node (ref "LED3") (pin "2") (pinfunction "VDD_2") (pintype "power_in"))
      (node (ref "LED4") (pin "2") (pinfunction "VDD_2") (pintype "power_in"))
      (node (ref "LED5") (pin "2") (pinfunction "VDD_2") (pintype "power_in"))
      (node (ref "LED6") (pin "2") (pinfunction "VDD_2") (pintype "power_in"))
      (node (ref "LED7") (pin "2") (pinfunction "VDD_2") (pintype "power_in"))
      (node (ref "LED8") (pin "2") (pinfunction "VDD_2") (pintype "power_in"))
      (node (ref "LED9") (pin "2") (pinfunction "VDD_2") (pintype "power_in"))
      (node (ref "Q1") (pin "3") (pinfunction "D_3") (pintype "passive"))
      (node (ref "THM1") (pin "2") (pinfunction "2_2") (pintype "passive"))
      (node (ref "U2") (pin "C") (pinfunction "C_C") (pintype "bidirectional"))
    )
    (net (code "63") (name "VBUS") (class "Default")
      (node (ref "C19") (pin "1") (pinfunction "1_1") (pintype "passive"))
      (node (ref "CN1") (pin "VBUS") (pinfunction "VBUS_VBUS") (pintype "power_in"))
      (node (ref "D1") (pin "A") (pinfunction "A_A") (pintype "passive"))
      (node (ref "U4") (pin "P$AD2") (pinfunction "VBUS_P$AD2") (pintype "power_in"))
    )
    (net (code "64") (name "VCC") (class "Default")
      (node (ref "C4") (pin "1") (pinfunction "1_1") (pintype "passive"))
      (node (ref "C5") (pin "1") (pinfunction "1_1") (pintype "passive"))
      (node (ref "F1") (pin "2") (pinfunction "2_2") (pintype "passive"))
      (node (ref "IC2") (pin "5") (pinfunction "VDD_5") (pintype "power_in"))
      (node (ref "U3") (pin "1") (pinfunction "IN_1") (pintype "power_in"))
      (node (ref "U3") (pin "3") (pinfunction "EN_3") (pintype "input"))
      (node (ref "VCC2") (pin "P$1") (pinfunction "SEW_P$1") (pintype "bidirectional"))
    )
    (net (code "65") (name "unconnected-(CN1-PadID)") (class "Default")
      (node (ref "CN1") (pin "ID") (pinfunction "ID_ID") (pintype "bidirectional"))
    )
    (net (code "66") (name "unconnected-(IC4-INT2-Pad9)") (class "Default")
      (node (ref "IC4") (pin "9") (pinfunction "INT2_9") (pintype "output"))
    )
    (net (code "67") (name "unconnected-(IC4-NC-Pad2)") (class "Default")
      (node (ref "IC4") (pin "2") (pinfunction "NC_2") (pintype "no_connect"))
    )
    (net (code "68") (name "unconnected-(IC4-NC-Pad3)") (class "Default")
      (node (ref "IC4") (pin "3") (pinfunction "NC_3") (pintype "no_connect"))
    )
    (net (code "69") (name "unconnected-(LED5-DO-Pad3)") (class "Default")
      (node (ref "LED5") (pin "3") (pinfunction "DO_3") (pintype "output"))
    )
    (net (code "70") (name "unconnected-(SWITCHA-O-PadO1)") (class "Default")
      (node (ref "SWITCH") (pin "O1") (pinfunction "O_O1") (pintype "passive"))
    )
    (net (code "71") (name "unconnected-(SWITCHB-O-PadO2)") (class "Default")
      (node (ref "SWITCH") (pin "O2") (pinfunction "O_O2") (pintype "passive"))
    )
    (net (code "72") (name "unconnected-(U3-P4-Pad4)") (class "Default")
      (node (ref "U3") (pin "4") (pinfunction "P4_4") (pintype "bidirectional"))
    )
    (net (code "73") (name "unconnected-(U4-DCC-PadP$B3)") (class "Default")
      (node (ref "U4") (pin "P$B3") (pinfunction "DCC_P$B3") (pintype "output"))
    )
    (net (code "74") (name "unconnected-(U4-P0.00{slash}XL1-PadP$D2)") (class "Default")
      (node (ref "U4") (pin "P$D2") (pinfunction "P0.00/XL1_P$D2") (pintype "bidirectional"))
    )
    (net (code "75") (name "unconnected-(U4-P0.01{slash}XL2-PadP$F2)") (class "Default")
      (node (ref "U4") (pin "P$F2") (pinfunction "P0.01/XL2_P$F2") (pintype "bidirectional"))
    )
    (net (code "76") (name "unconnected-(U4-P0.07-PadP$M2)") (class "Default")
      (node (ref "U4") (pin "P$M2") (pinfunction "P0.07_P$M2") (pintype "bidirectional"))
    )
    (net (code "77") (name "unconnected-(U4-P0.08-PadP$N1)") (class "Default")
      (node (ref "U4") (pin "P$N1") (pinfunction "P0.08_P$N1") (pintype "bidirectional"))
    )
    (net (code "78") (name "unconnected-(U4-P0.11-PadP$T2)") (class "Default")
      (node (ref "U4") (pin "P$T2") (pinfunction "P0.11_P$T2") (pintype "bidirectional"))
    )
    (net (code "79") (name "unconnected-(U4-P0.12-PadP$U1)") (class "Default")
      (node (ref "U4") (pin "P$U1") (pinfunction "P0.12_P$U1") (pintype "bidirectional"))
    )
    (net (code "80") (name "unconnected-(U4-P0.20-PadP$AD16)") (class "Default")
      (node (ref "U4") (pin "P$AD16") (pinfunction "P0.20_P$AD16") (pintype "bidirectional"))
    )
    (net (code "81") (name "unconnected-(U4-P0.24-PadP$AD20)") (class "Default")
      (node (ref "U4") (pin "P$AD20") (pinfunction "P0.24_P$AD20") (pintype "bidirectional"))
    )
    (net (code "82") (name "unconnected-(U4-P0.25-PadP$AC21)") (class "Default")
      (node (ref "U4") (pin "P$AC21") (pinfunction "P0.25_P$AC21") (pintype "bidirectional"))
    )
    (net (code "83") (name "unconnected-(U4-P0.27-PadP$H2)") (class "Default")
      (node (ref "U4") (pin "P$H2") (pinfunction "P0.27_P$H2") (pintype "bidirectional"))
    )
    (net (code "84") (name "unconnected-(U4-P1.08-PadP$P2)") (class "Default")
      (node (ref "U4") (pin "P$P2") (pinfunction "P1.08_P$P2") (pintype "bidirectional"))
    )
    (net (code "85") (name "unconnected-(U4-P1.09-PadP$R1)") (class "Default")
      (node (ref "U4") (pin "P$R1") (pinfunction "P1.09_P$R1") (pintype "bidirectional"))
    )
    (net (code "86") (name "~{RESET}") (class "Default")
      (node (ref "RESET") (pin "A") (pinfunction "P_A") (pintype "passive"))
      (node (ref "RESET") (pin "A'") (pinfunction "P1_A'") (pintype "passive"))
      (node (ref "TP3") (pin "P$1") (pinfunction "P$1_P$1") (pintype "bidirectional"))
      (node (ref "U4") (pin "P$AC13") (pinfunction "P0.18/RESET_P$AC13") (pintype "bidirectional"))
    )
  )
)
